# main_board.net
KiCad netlist of a schematic drawn in EAGLE
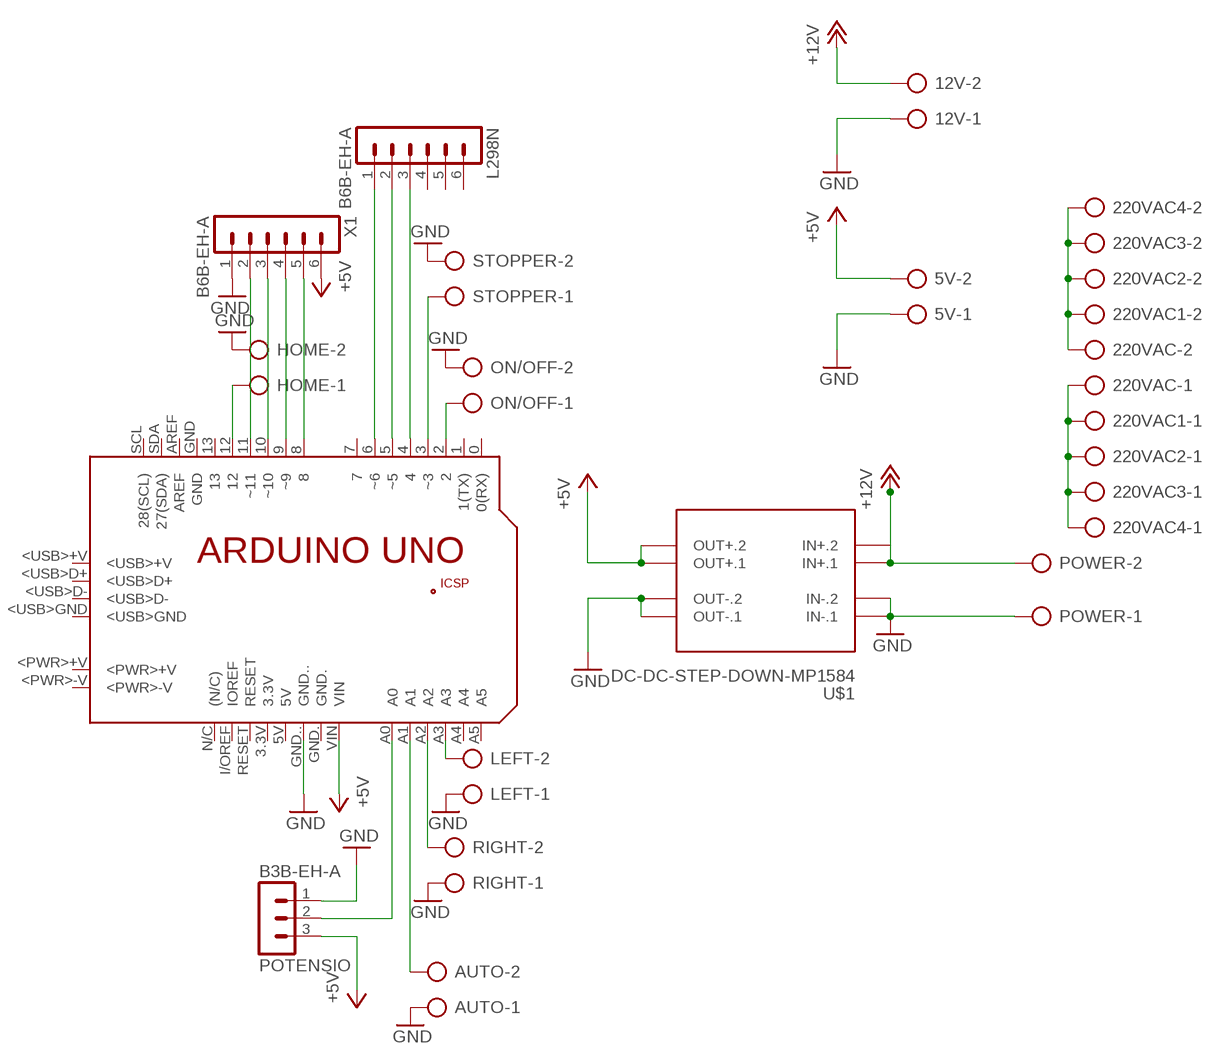
[diagram p0: schematic, sheet 1]

(export (version "E")
  (design (tool "Eeschema 10.0.6"))
  (components
    (comp (ref "5V")
      (value "AK500/2-H")
      (footprint "eagle-import:AK500_2-H")
      (libsource (lib "eagle-import") (part "AK500/2-H"))
    )
    (comp (ref "12V")
      (value "AK500/2-H")
      (footprint "eagle-import:AK500_2-H")
      (libsource (lib "eagle-import") (part "AK500/2-H"))
    )
    (comp (ref "220VAC")
      (value "AK500/2-H")
      (footprint "eagle-import:AK500_2-H")
      (libsource (lib "eagle-import") (part "AK500/2-H"))
    )
    (comp (ref "220VAC1")
      (value "AK500/2-H")
      (footprint "eagle-import:AK500_2-H")
      (libsource (lib "eagle-import") (part "AK500/2-H"))
    )
    (comp (ref "220VAC2")
      (value "AK500/2-H")
      (footprint "eagle-import:AK500_2-H")
      (libsource (lib "eagle-import") (part "AK500/2-H"))
    )
    (comp (ref "220VAC3")
      (value "AK500/2-H")
      (footprint "eagle-import:AK500_2-H")
      (libsource (lib "eagle-import") (part "AK500/2-H"))
    )
    (comp (ref "220VAC4")
      (value "AK500/2-H")
      (footprint "eagle-import:AK500_2-H")
      (libsource (lib "eagle-import") (part "AK500/2-H"))
    )
    (comp (ref "AUTO")
      (value "AK500/2-H")
      (footprint "eagle-import:AK500_2-H")
      (libsource (lib "eagle-import") (part "AK500/2-H"))
    )
    (comp (ref "HOME")
      (value "AK500/2-H")
      (footprint "eagle-import:AK500_2-H")
      (libsource (lib "eagle-import") (part "AK500/2-H"))
    )
    (comp (ref "L298N")
      (value "B6B-EH-A")
      (footprint "eagle-import:B6B-EH-A")
      (libsource (lib "eagle-import") (part "B6B-EH-A"))
    )
    (comp (ref "LEFT")
      (value "AK500/2-H")
      (footprint "eagle-import:AK500_2-H")
      (libsource (lib "eagle-import") (part "AK500/2-H"))
    )
    (comp (ref "ON/OFF")
      (value "AK500/2-H")
      (footprint "eagle-import:AK500_2-H")
      (libsource (lib "eagle-import") (part "AK500/2-H"))
    )
    (comp (ref "PCB1")
      (value "ARDUINO_UNO")
      (footprint "eagle-import:ARDUINO_UNO")
      (libsource (lib "eagle-import") (part "ARDUINO_UNO"))
    )
    (comp (ref "POTENSIO")
      (value "B3B-EH-A")
      (footprint "eagle-import:B3B-EH-A")
      (libsource (lib "eagle-import") (part "B3B-EH-A"))
    )
    (comp (ref "POWER")
      (value "AK500/2-H")
      (footprint "eagle-import:AK500_2-H")
      (libsource (lib "eagle-import") (part "AK500/2-H"))
    )
    (comp (ref "RIGHT")
      (value "AK500/2-H")
      (footprint "eagle-import:AK500_2-H")
      (libsource (lib "eagle-import") (part "AK500/2-H"))
    )
    (comp (ref "STOPPER")
      (value "AK500/2-H")
      (footprint "eagle-import:AK500_2-H")
      (libsource (lib "eagle-import") (part "AK500/2-H"))
    )
    (comp (ref "U$1")
      (value "DC-DC-STEP-DOWN-MP1584")
      (footprint "eagle-import:DC-DC-STEP-DOWN-MP1584")
      (libsource (lib "eagle-import") (part "DC-DC-STEP-DOWN-MP1584"))
    )
    (comp (ref "X1")
      (value "B6B-EH-A")
      (footprint "eagle-import:B6B-EH-A")
      (libsource (lib "eagle-import") (part "B6B-EH-A"))
    )
  )
  (nets
    (net (code "1") (name "+5V") (class "Default")
      (node (ref "5V") (pin "2") (pinfunction "KL_2") (pintype "passive"))
      (node (ref "PCB1") (pin "VIN") (pinfunction "VIN_VIN") (pintype "bidirectional"))
      (node (ref "POTENSIO") (pin "3") (pinfunction "3_3") (pintype "passive"))
      (node (ref "U$1") (pin "OUT+.1") (pinfunction "OUT+.1_OUT+.1") (pintype "bidirectional"))
      (node (ref "U$1") (pin "OUT+.2") (pinfunction "OUT+.2_OUT+.2") (pintype "bidirectional"))
      (node (ref "X1") (pin "6") (pinfunction "6_6") (pintype "passive"))
    )
    (net (code "2") (name "+12V") (class "Default")
      (node (ref "12V") (pin "2") (pinfunction "KL_2") (pintype "passive"))
      (node (ref "POWER") (pin "2") (pinfunction "KL_2") (pintype "passive"))
      (node (ref "U$1") (pin "IN+.1") (pinfunction "IN+.1_IN+.1") (pintype "bidirectional"))
      (node (ref "U$1") (pin "IN+.2") (pinfunction "IN+.2_IN+.2") (pintype "bidirectional"))
    )
    (net (code "3") (name "GND") (class "Default")
      (node (ref "12V") (pin "1") (pinfunction "KL_1") (pintype "passive"))
      (node (ref "5V") (pin "1") (pinfunction "KL_1") (pintype "passive"))
      (node (ref "AUTO") (pin "1") (pinfunction "KL_1") (pintype "passive"))
      (node (ref "HOME") (pin "2") (pinfunction "KL_2") (pintype "passive"))
      (node (ref "LEFT") (pin "1") (pinfunction "KL_1") (pintype "passive"))
      (node (ref "ON/OFF") (pin "2") (pinfunction "KL_2") (pintype "passive"))
      (node (ref "PCB1") (pin "GND..") (pinfunction "GND.._GND..") (pintype "bidirectional"))
      (node (ref "POTENSIO") (pin "1") (pinfunction "1_1") (pintype "passive"))
      (node (ref "POWER") (pin "1") (pinfunction "KL_1") (pintype "passive"))
      (node (ref "RIGHT") (pin "1") (pinfunction "KL_1") (pintype "passive"))
      (node (ref "STOPPER") (pin "2") (pinfunction "KL_2") (pintype "passive"))
      (node (ref "U$1") (pin "IN-.1") (pinfunction "IN-.1_IN-.1") (pintype "bidirectional"))
      (node (ref "U$1") (pin "IN-.2") (pinfunction "IN-.2_IN-.2") (pintype "bidirectional"))
      (node (ref "U$1") (pin "OUT-.1") (pinfunction "OUT-.1_OUT-.1") (pintype "bidirectional"))
      (node (ref "U$1") (pin "OUT-.2") (pinfunction "OUT-.2_OUT-.2") (pintype "bidirectional"))
      (node (ref "X1") (pin "1") (pinfunction "1_1") (pintype "passive"))
    )
    (net (code "4") (name "Net-(220VAC1A-KL)") (class "Default")
      (node (ref "220VAC") (pin "1") (pinfunction "KL_1") (pintype "passive"))
      (node (ref "220VAC1") (pin "1") (pinfunction "KL_1") (pintype "passive"))
      (node (ref "220VAC2") (pin "1") (pinfunction "KL_1") (pintype "passive"))
      (node (ref "220VAC3") (pin "1") (pinfunction "KL_1") (pintype "passive"))
      (node (ref "220VAC4") (pin "1") (pinfunction "KL_1") (pintype "passive"))
    )
    (net (code "5") (name "Net-(220VAC1B-KL)") (class "Default")
      (node (ref "220VAC") (pin "2") (pinfunction "KL_2") (pintype "passive"))
      (node (ref "220VAC1") (pin "2") (pinfunction "KL_2") (pintype "passive"))
      (node (ref "220VAC2") (pin "2") (pinfunction "KL_2") (pintype "passive"))
      (node (ref "220VAC3") (pin "2") (pinfunction "KL_2") (pintype "passive"))
      (node (ref "220VAC4") (pin "2") (pinfunction "KL_2") (pintype "passive"))
    )
    (net (code "6") (name "Net-(AUTOB-KL)") (class "Default")
      (node (ref "AUTO") (pin "2") (pinfunction "KL_2") (pintype "passive"))
      (node (ref "PCB1") (pin "A1") (pinfunction "A1_A1") (pintype "bidirectional"))
    )
    (net (code "7") (name "Net-(HOMEA-KL)") (class "Default")
      (node (ref "HOME") (pin "1") (pinfunction "KL_1") (pintype "passive"))
      (node (ref "PCB1") (pin "12") (pinfunction "12_12") (pintype "bidirectional"))
    )
    (net (code "8") (name "Net-(L298N-Pad3)") (class "Default")
      (node (ref "L298N") (pin "3") (pinfunction "3_3") (pintype "passive"))
      (node (ref "PCB1") (pin "4") (pinfunction "4_4") (pintype "bidirectional"))
    )
    (net (code "9") (name "Net-(LEFTB-KL)") (class "Default")
      (node (ref "LEFT") (pin "2") (pinfunction "KL_2") (pintype "passive"))
      (node (ref "PCB1") (pin "A3") (pinfunction "A3_A3") (pintype "bidirectional"))
    )
    (net (code "10") (name "Net-(ON/OFFA-KL)") (class "Default")
      (node (ref "ON/OFF") (pin "1") (pinfunction "KL_1") (pintype "passive"))
      (node (ref "PCB1") (pin "2") (pinfunction "2_2") (pintype "bidirectional"))
    )
    (net (code "11") (name "Net-(PCB1-Pad8)") (class "Default")
      (node (ref "PCB1") (pin "8") (pinfunction "8_8") (pintype "bidirectional"))
      (node (ref "X1") (pin "5") (pinfunction "5_5") (pintype "passive"))
    )
    (net (code "12") (name "Net-(PCB1-PadA0)") (class "Default")
      (node (ref "PCB1") (pin "A0") (pinfunction "A0_A0") (pintype "bidirectional"))
      (node (ref "POTENSIO") (pin "2") (pinfunction "2_2") (pintype "passive"))
    )
    (net (code "13") (name "Net-(PCB1-~{3})") (class "Default")
      (node (ref "PCB1") (pin "3") (pinfunction "~{3}_3") (pintype "bidirectional"))
      (node (ref "STOPPER") (pin "1") (pinfunction "KL_1") (pintype "passive"))
    )
    (net (code "14") (name "Net-(PCB1-~{5})") (class "Default")
      (node (ref "L298N") (pin "2") (pinfunction "2_2") (pintype "passive"))
      (node (ref "PCB1") (pin "5") (pinfunction "~{5}_5") (pintype "bidirectional"))
    )
    (net (code "15") (name "Net-(PCB1-~{6})") (class "Default")
      (node (ref "L298N") (pin "1") (pinfunction "1_1") (pintype "passive"))
      (node (ref "PCB1") (pin "6") (pinfunction "~{6}_6") (pintype "bidirectional"))
    )
    (net (code "16") (name "Net-(PCB1-~{9})") (class "Default")
      (node (ref "PCB1") (pin "9") (pinfunction "~{9}_9") (pintype "bidirectional"))
      (node (ref "X1") (pin "4") (pinfunction "4_4") (pintype "passive"))
    )
    (net (code "17") (name "Net-(PCB1-~{10})") (class "Default")
      (node (ref "PCB1") (pin "10") (pinfunction "~{10}_10") (pintype "bidirectional"))
      (node (ref "X1") (pin "3") (pinfunction "3_3") (pintype "passive"))
    )
    (net (code "18") (name "Net-(PCB1-~{11})") (class "Default")
      (node (ref "PCB1") (pin "11") (pinfunction "~{11}_11") (pintype "bidirectional"))
      (node (ref "X1") (pin "2") (pinfunction "2_2") (pintype "passive"))
    )
    (net (code "19") (name "Net-(RIGHTB-KL)") (class "Default")
      (node (ref "PCB1") (pin "A2") (pinfunction "A2_A2") (pintype "bidirectional"))
      (node (ref "RIGHT") (pin "2") (pinfunction "KL_2") (pintype "passive"))
    )
    (net (code "20") (name "unconnected-(L298N-Pad4)") (class "Default")
      (node (ref "L298N") (pin "4") (pinfunction "4_4") (pintype "passive"))
    )
    (net (code "21") (name "unconnected-(L298N-Pad5)") (class "Default")
      (node (ref "L298N") (pin "5") (pinfunction "5_5") (pintype "passive"))
    )
    (net (code "22") (name "unconnected-(L298N-Pad6)") (class "Default")
      (node (ref "L298N") (pin "6") (pinfunction "6_6") (pintype "passive"))
    )
    (net (code "23") (name "unconnected-(PCB1-(N{slash}C)-PadN{slash}C)") (class "Default")
      (node (ref "PCB1") (pin "N/C") (pinfunction "(N/C)_N/C") (pintype "bidirectional"))
    )
    (net (code "24") (name "unconnected-(PCB1-0(RX)-Pad0)") (class "Default")
      (node (ref "PCB1") (pin "0") (pinfunction "0(RX)_0") (pintype "bidirectional"))
    )
    (net (code "25") (name "unconnected-(PCB1-1(TX)-Pad1)") (class "Default")
      (node (ref "PCB1") (pin "1") (pinfunction "1(TX)_1") (pintype "bidirectional"))
    )
    (net (code "26") (name "unconnected-(PCB1-27(SDA)-PadSDA)") (class "Default")
      (node (ref "PCB1") (pin "SDA") (pinfunction "27(SDA)_SDA") (pintype "bidirectional"))
    )
    (net (code "27") (name "unconnected-(PCB1-28(SCL)-PadSCL)") (class "Default")
      (node (ref "PCB1") (pin "SCL") (pinfunction "28(SCL)_SCL") (pintype "bidirectional"))
    )
    (net (code "28") (name "unconnected-(PCB1-IOREF-PadI{slash}OREF)") (class "Default")
      (node (ref "PCB1") (pin "I/OREF") (pinfunction "IOREF_I/OREF") (pintype "bidirectional"))
    )
    (net (code "29") (name "unconnected-(PCB1-Pad+5V)") (class "Default")
      (node (ref "PCB1") (pin "+5V") (pinfunction "+5V_+5V") (pintype "bidirectional"))
    )
    (net (code "30") (name "unconnected-(PCB1-Pad3.3V)") (class "Default")
      (node (ref "PCB1") (pin "3.3V") (pinfunction "3.3V_3.3V") (pintype "bidirectional"))
    )
    (net (code "31") (name "unconnected-(PCB1-Pad5V)") (class "Default")
      (node (ref "PCB1") (pin "5V") (pinfunction "5V_5V") (pintype "bidirectional"))
    )
    (net (code "32") (name "unconnected-(PCB1-Pad7)") (class "Default")
      (node (ref "PCB1") (pin "7") (pinfunction "7_7") (pintype "bidirectional"))
    )
    (net (code "33") (name "unconnected-(PCB1-Pad13)") (class "Default")
      (node (ref "PCB1") (pin "13") (pinfunction "13_13") (pintype "bidirectional"))
    )
    (net (code "34") (name "unconnected-(PCB1-Pad<PWR>+V)") (class "Default")
      (node (ref "PCB1") (pin "<PWR>+V") (pinfunction "<PWR>+V_<PWR>+V") (pintype "bidirectional"))
    )
    (net (code "35") (name "unconnected-(PCB1-Pad<PWR>-V)") (class "Default")
      (node (ref "PCB1") (pin "<PWR>-V") (pinfunction "<PWR>-V_<PWR>-V") (pintype "bidirectional"))
    )
    (net (code "36") (name "unconnected-(PCB1-Pad<USB>+V)") (class "Default")
      (node (ref "PCB1") (pin "<USB>+V") (pinfunction "<USB>+V_<USB>+V") (pintype "bidirectional"))
    )
    (net (code "37") (name "unconnected-(PCB1-Pad<USB>D+)") (class "Default")
      (node (ref "PCB1") (pin "<USB>D+") (pinfunction "<USB>D+_<USB>D+") (pintype "bidirectional"))
    )
    (net (code "38") (name "unconnected-(PCB1-Pad<USB>D-)") (class "Default")
      (node (ref "PCB1") (pin "<USB>D-") (pinfunction "<USB>D-_<USB>D-") (pintype "bidirectional"))
    )
    (net (code "39") (name "unconnected-(PCB1-Pad<USB>GND)") (class "Default")
      (node (ref "PCB1") (pin "<USB>GND") (pinfunction "<USB>GND_<USB>GND") (pintype "bidirectional"))
    )
    (net (code "40") (name "unconnected-(PCB1-PadA4)") (class "Default")
      (node (ref "PCB1") (pin "A4") (pinfunction "A4_A4") (pintype "bidirectional"))
    )
    (net (code "41") (name "unconnected-(PCB1-PadA5)") (class "Default")
      (node (ref "PCB1") (pin "A5") (pinfunction "A5_A5") (pintype "bidirectional"))
    )
    (net (code "42") (name "unconnected-(PCB1-PadAREF)") (class "Default")
      (node (ref "PCB1") (pin "AREF") (pinfunction "AREF_AREF") (pintype "bidirectional"))
    )
    (net (code "43") (name "unconnected-(PCB1-PadGND)") (class "Default")
      (node (ref "PCB1") (pin "GND") (pinfunction "GND_GND") (pintype "bidirectional"))
    )
    (net (code "44") (name "unconnected-(PCB1-PadGND.)") (class "Default")
      (node (ref "PCB1") (pin "GND.") (pinfunction "GND._GND.") (pintype "bidirectional"))
    )
    (net (code "45") (name "unconnected-(PCB1-PadGND_)") (class "Default")
      (node (ref "PCB1") (pin "GND_") (pinfunction "GND__GND_") (pintype "bidirectional"))
    )
    (net (code "46") (name "unconnected-(PCB1-PadMISO)") (class "Default")
      (node (ref "PCB1") (pin "MISO") (pinfunction "MISO_MISO") (pintype "bidirectional"))
    )
    (net (code "47") (name "unconnected-(PCB1-PadMOSI)") (class "Default")
      (node (ref "PCB1") (pin "MOSI") (pinfunction "MOSI_MOSI") (pintype "bidirectional"))
    )
    (net (code "48") (name "unconnected-(PCB1-PadRESET)") (class "Default")
      (node (ref "PCB1") (pin "RESET") (pinfunction "RESET_RESET") (pintype "bidirectional"))
    )
    (net (code "49") (name "unconnected-(PCB1-PadRESET.)") (class "Default")
      (node (ref "PCB1") (pin "RESET.") (pinfunction "RESET._RESET.") (pintype "bidirectional"))
    )
    (net (code "50") (name "unconnected-(PCB1-PadSCK)") (class "Default")
      (node (ref "PCB1") (pin "SCK") (pinfunction "SCK_SCK") (pintype "bidirectional"))
    )
  )
)
